# PortBreakoutCapacitive_r1.net
KiCad netlist of a schematic drawn in EAGLE
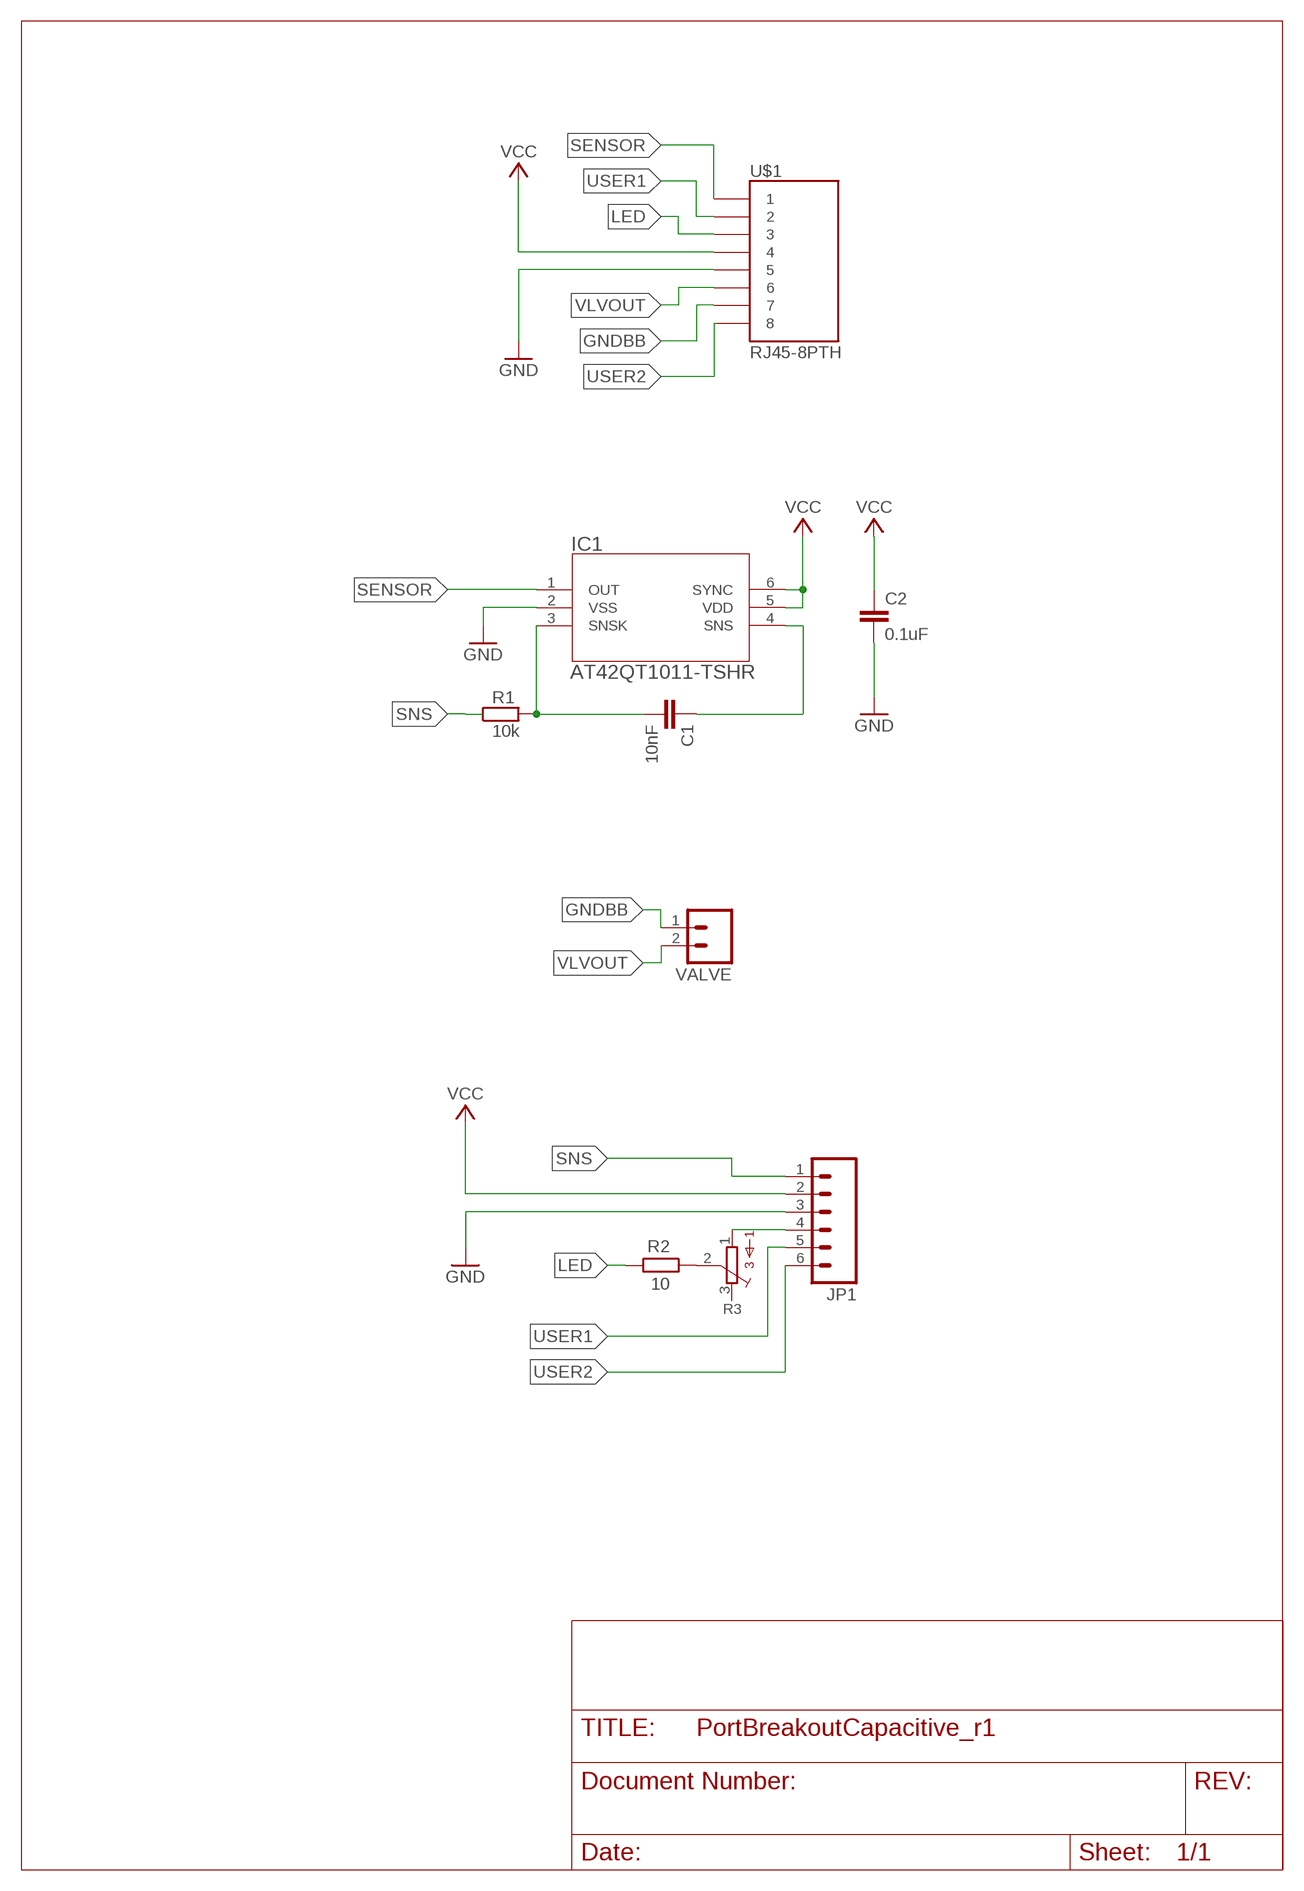
[diagram p0: schematic, sheet 1]

(export (version "E")
  (design (tool "Eeschema 10.0.6"))
  (components
    (comp (ref "C1")
      (value "10nF")
      (footprint "eagle-import:C1206")
      (libsource (lib "eagle-import") (part "C-EUC1206"))
    )
    (comp (ref "C2")
      (value "0.1uF")
      (footprint "eagle-import:C1206")
      (libsource (lib "eagle-import") (part "C-EUC1206"))
    )
    (comp (ref "IC1")
      (value "AT42QT1011-TSHR")
      (footprint "eagle-import:6ST1_ATM")
      (fields (field (name "MANUFACTURER_PART_NUMBER") "AT42QT1010-TSHR"))
      (libsource (lib "eagle-import") (part "AT42QT1010-TSHR"))
    )
    (comp (ref "JP1")
      (value "M063.5MM-6")
      (footprint "eagle-import:SCREWTERMINAL-3.5MM-6")
      (libsource (lib "eagle-import") (part "M063.5MM-6"))
    )
    (comp (ref "R1")
      (value "10k")
      (footprint "eagle-import:R1206")
      (libsource (lib "eagle-import") (part "R-EU_R1206"))
    )
    (comp (ref "R2")
      (value "10")
      (footprint "eagle-import:R1206")
      (libsource (lib "eagle-import") (part "R-EU_R1206"))
    )
    (comp (ref "R3")
      (value "3362R")
      (footprint "eagle-import:3362R")
      (libsource (lib "eagle-import") (part "3362R"))
    )
    (comp (ref "U$1")
      (value "RJ45-8PTH")
      (footprint "eagle-import:RJ45-8")
      (libsource (lib "eagle-import") (part "RJ45-8PTH"))
    )
    (comp (ref "VALVE")
      (value "M023.5MM_LOCK")
      (footprint "eagle-import:SCREWTERMINAL-3.5MM-2_LOCK")
      (libsource (lib "eagle-import") (part "M023.5MM_LOCK"))
    )
  )
  (nets
    (net (code "1") (name "GND") (class "Default")
      (node (ref "C2") (pin "2") (pinfunction "2_2") (pintype "passive"))
      (node (ref "IC1") (pin "2") (pinfunction "VSS_2") (pintype "power_in"))
      (node (ref "JP1") (pin "3") (pinfunction "3_3") (pintype "passive"))
      (node (ref "U$1") (pin "5") (pinfunction "5_5") (pintype "bidirectional"))
    )
    (net (code "2") (name "GNDBB") (class "Default")
      (node (ref "U$1") (pin "7") (pinfunction "7_7") (pintype "bidirectional"))
      (node (ref "VALVE") (pin "1") (pinfunction "1_1") (pintype "passive"))
    )
    (net (code "3") (name "LED") (class "Default")
      (node (ref "R2") (pin "2") (pinfunction "2_2") (pintype "passive"))
      (node (ref "U$1") (pin "3") (pinfunction "3_3") (pintype "bidirectional"))
    )
    (net (code "4") (name "Net-(IC1-SNS)") (class "Default")
      (node (ref "C1") (pin "1") (pinfunction "1_1") (pintype "passive"))
      (node (ref "IC1") (pin "4") (pinfunction "SNS_4") (pintype "bidirectional"))
    )
    (net (code "5") (name "Net-(IC1-SNSK)") (class "Default")
      (node (ref "C1") (pin "2") (pinfunction "2_2") (pintype "passive"))
      (node (ref "IC1") (pin "3") (pinfunction "SNSK_3") (pintype "bidirectional"))
      (node (ref "R1") (pin "2") (pinfunction "2_2") (pintype "passive"))
    )
    (net (code "6") (name "Net-(JP1-Pad4)") (class "Default")
      (node (ref "JP1") (pin "4") (pinfunction "4_4") (pintype "passive"))
      (node (ref "R3") (pin "1") (pinfunction "1_1") (pintype "passive"))
    )
    (net (code "7") (name "Net-(R2-Pad1)") (class "Default")
      (node (ref "R2") (pin "1") (pinfunction "1_1") (pintype "passive"))
      (node (ref "R3") (pin "2") (pinfunction "2_2") (pintype "passive"))
    )
    (net (code "8") (name "SENSOR") (class "Default")
      (node (ref "IC1") (pin "1") (pinfunction "OUT_1") (pintype "output"))
      (node (ref "U$1") (pin "1") (pinfunction "1_1") (pintype "bidirectional"))
    )
    (net (code "9") (name "SNS") (class "Default")
      (node (ref "JP1") (pin "1") (pinfunction "1_1") (pintype "passive"))
      (node (ref "R1") (pin "1") (pinfunction "1_1") (pintype "passive"))
    )
    (net (code "10") (name "USER1") (class "Default")
      (node (ref "JP1") (pin "5") (pinfunction "5_5") (pintype "passive"))
      (node (ref "U$1") (pin "2") (pinfunction "2_2") (pintype "bidirectional"))
    )
    (net (code "11") (name "USER2") (class "Default")
      (node (ref "JP1") (pin "6") (pinfunction "6_6") (pintype "passive"))
      (node (ref "U$1") (pin "8") (pinfunction "8_8") (pintype "bidirectional"))
    )
    (net (code "12") (name "VCC") (class "Default")
      (node (ref "C2") (pin "1") (pinfunction "1_1") (pintype "passive"))
      (node (ref "IC1") (pin "5") (pinfunction "VDD_5") (pintype "power_in"))
      (node (ref "IC1") (pin "6") (pinfunction "SYNC_6") (pintype "input"))
      (node (ref "JP1") (pin "2") (pinfunction "2_2") (pintype "passive"))
      (node (ref "U$1") (pin "4") (pinfunction "4_4") (pintype "bidirectional"))
    )
    (net (code "13") (name "VLVOUT") (class "Default")
      (node (ref "U$1") (pin "6") (pinfunction "6_6") (pintype "bidirectional"))
      (node (ref "VALVE") (pin "2") (pinfunction "2_2") (pintype "passive"))
    )
    (net (code "14") (name "unconnected-(R3-Pad3)") (class "Default")
      (node (ref "R3") (pin "3") (pinfunction "3_3") (pintype "passive"))
    )
  )
)
